# Sync_In.net
KiCad netlist of a schematic drawn in Altium Designer
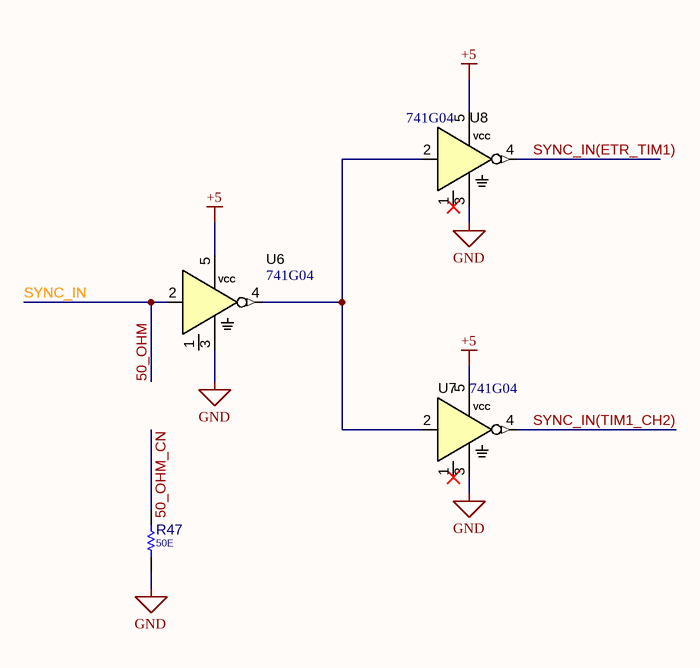
[diagram p0: Sync In.SchDoc]

(export (version "E")
  (design (tool "Eeschema 10.0.6"))
  (components
    (comp (ref "R47")
      (value "50E")
      (footprint "R0603")
      (description "RESISTOR, SMD")
      (libsource (lib "passive_smd") (part "RES_SMD_0603"))
    )
    (comp (ref "U6")
      (value "741G04")
      (footprint "SOT353_5")
      (description "GATE, NOT, SINGLE, SOT353 SMD")
      (fields (field (name "MANF") "Texas Instruments") (field (name "MANF_P#") "SN74LVC1GU04DCK"))
      (libsource (lib "logic_gate") (part "NOT_SN74LVC1G04_SOT353"))
    )
    (comp (ref "U7")
      (value "741G04")
      (footprint "SOT353_5")
      (description "GATE, NOT, SINGLE, SOT353 SMD")
      (fields (field (name "MANF") "Texas Instruments") (field (name "MANF_P#") "SN74LVC1GU04DCK"))
      (libsource (lib "logic_gate") (part "NOT_SN74LVC1G04_SOT353"))
    )
    (comp (ref "U8")
      (value "741G04")
      (footprint "SOT353_5")
      (description "GATE, NOT, SINGLE, SOT353 SMD")
      (fields (field (name "MANF") "Texas Instruments") (field (name "MANF_P#") "SN74LVC1GU04DCK"))
      (libsource (lib "logic_gate") (part "NOT_SN74LVC1G04_SOT353"))
    )
  )
  (nets
    (net (code "1") (name "+5") (class "Default")
      (node (ref "U6") (pin "5") (pinfunction "VCC_5") (pintype "power_in"))
      (node (ref "U7") (pin "5") (pinfunction "VCC_5") (pintype "power_in"))
      (node (ref "U8") (pin "5") (pinfunction "VCC_5") (pintype "power_in"))
    )
    (net (code "2") (name "/50_OHM") (class "Default")
      (node (ref "U6") (pin "2") (pinfunction "A_2") (pintype "passive"))
    )
    (net (code "3") (name "/50_OHM_CN") (class "Default")
      (node (ref "R47") (pin "1") (pinfunction "1_1") (pintype "passive"))
    )
    (net (code "4") (name "/SYNC_IN(ETR_TIM1)") (class "Default")
      (node (ref "U8") (pin "4") (pinfunction "Y_4") (pintype "output"))
    )
    (net (code "5") (name "/SYNC_IN(TIM1_CH2)") (class "Default")
      (node (ref "U7") (pin "4") (pinfunction "Y_4") (pintype "output"))
    )
    (net (code "6") (name "GND") (class "Default")
      (node (ref "R47") (pin "2") (pinfunction "2_2") (pintype "passive"))
      (node (ref "U6") (pin "3") (pinfunction "GND_3") (pintype "power_in"))
      (node (ref "U7") (pin "3") (pinfunction "GND_3") (pintype "power_in"))
      (node (ref "U8") (pin "3") (pinfunction "GND_3") (pintype "power_in"))
    )
    (net (code "7") (name "Net-(U6-Y)") (class "Default")
      (node (ref "U6") (pin "4") (pinfunction "Y_4") (pintype "output"))
      (node (ref "U7") (pin "2") (pinfunction "A_2") (pintype "passive"))
      (node (ref "U8") (pin "2") (pinfunction "A_2") (pintype "passive"))
    )
    (net (code "8") (name "unconnected-(U6-NC-Pad1)") (class "Default")
      (node (ref "U6") (pin "1") (pinfunction "NC_1") (pintype "passive"))
    )
    (net (code "9") (name "unconnected-(U7-NC-Pad1)") (class "Default")
      (node (ref "U7") (pin "1") (pinfunction "NC_1") (pintype "passive+no_connect"))
    )
    (net (code "10") (name "unconnected-(U8-NC-Pad1)") (class "Default")
      (node (ref "U8") (pin "1") (pinfunction "NC_1") (pintype "passive+no_connect"))
    )
  )
)
